# jduino.net
KiCad netlist of a schematic drawn in EAGLE
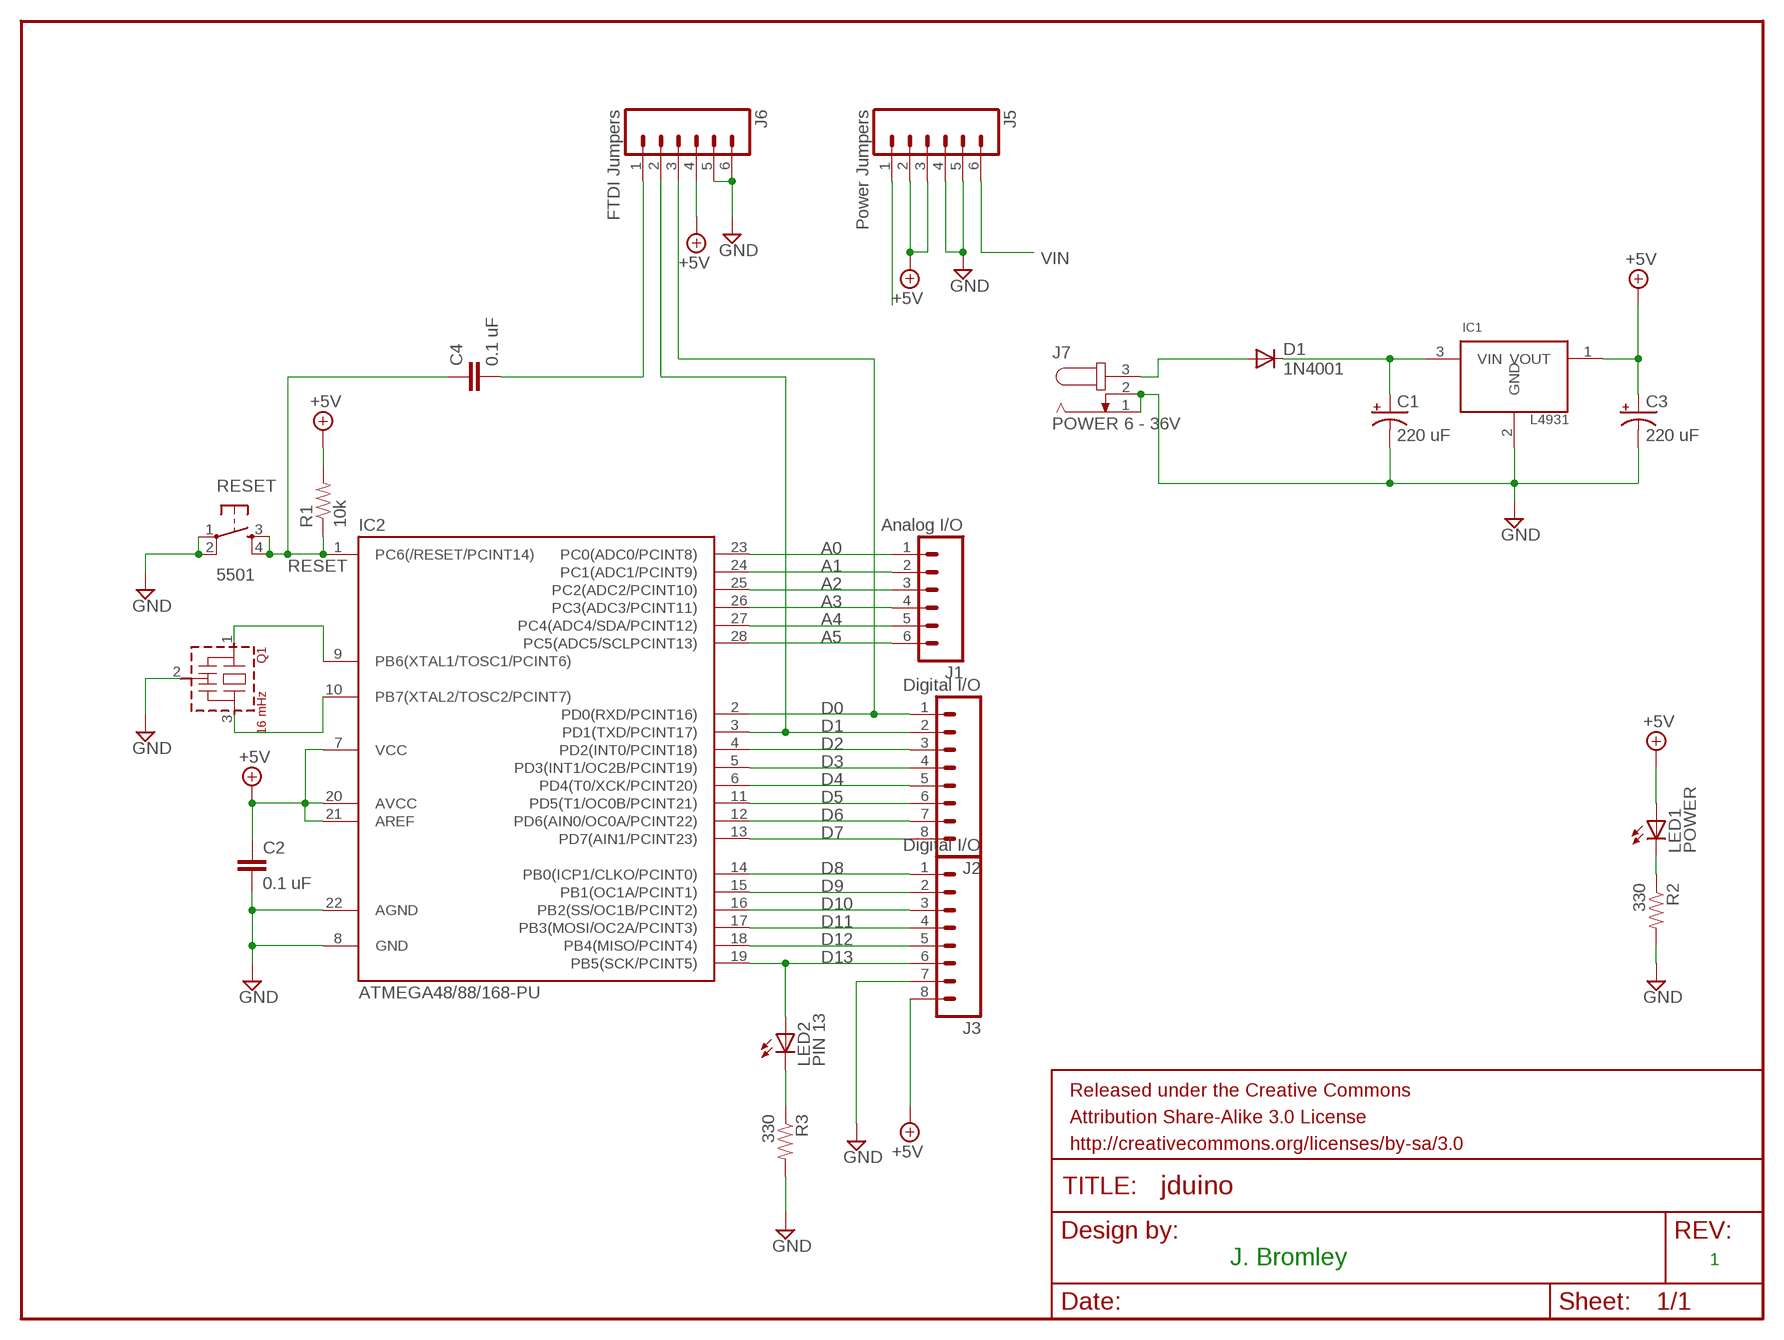
[diagram p0: schematic, sheet 1]

(export (version "E")
  (design (tool "Eeschema 10.0.6"))
  (components
    (comp (ref "C1")
      (value "220 uF")
      (footprint "eagle-import:CPOL-RADIAL-10UF-25V")
      (libsource (lib "eagle-import") (part "CAP_POLPTH2"))
    )
    (comp (ref "C2")
      (value "0.1 uF")
      (footprint "eagle-import:CAP-PTH-SMALL")
      (libsource (lib "eagle-import") (part "CAPPTH"))
    )
    (comp (ref "C3")
      (value "220 uF")
      (footprint "eagle-import:CPOL-RADIAL-10UF-25V")
      (libsource (lib "eagle-import") (part "CAP_POLPTH2"))
    )
    (comp (ref "C4")
      (value "0.1 uF")
      (footprint "eagle-import:CAP-PTH-SMALL")
      (libsource (lib "eagle-import") (part "CAPPTH"))
    )
    (comp (ref "D1")
      (value "1N4001")
      (footprint "eagle-import:DIODE-1N4001")
      (libsource (lib "eagle-import") (part "DIODEPTH"))
    )
    (comp (ref "IC1")
      (value "L4931")
      (footprint "eagle-import:TO-92")
      (libsource (lib "eagle-import") (part "L4931"))
    )
    (comp (ref "IC2")
      (value "ATMEGA48/88/168-PU")
      (footprint "eagle-import:DIL28-3")
      (libsource (lib "eagle-import") (part "ATMEGA48/88/168-PU"))
    )
    (comp (ref "J1")
      (value "Analog I/O")
      (footprint "eagle-import:1X06")
      (libsource (lib "eagle-import") (part "M06SIP"))
    )
    (comp (ref "J2")
      (value "Digital I/O")
      (footprint "eagle-import:1X08")
      (libsource (lib "eagle-import") (part "M08"))
    )
    (comp (ref "J3")
      (value "Digital I/O")
      (footprint "eagle-import:1X08")
      (libsource (lib "eagle-import") (part "M08"))
    )
    (comp (ref "J5")
      (value "Power Jumpers")
      (footprint "eagle-import:1X06")
      (libsource (lib "eagle-import") (part "M06SIP"))
    )
    (comp (ref "J6")
      (value "FTDI Jumpers")
      (footprint "eagle-import:1X06")
      (libsource (lib "eagle-import") (part "M06SIP"))
    )
    (comp (ref "J7")
      (value "POWER 6 - 36V")
      (footprint "eagle-import:SPC4078")
      (libsource (lib "eagle-import") (part "JACK-PLUG1"))
    )
    (comp (ref "LED1")
      (value "POWER")
      (footprint "eagle-import:LED3MM")
      (libsource (lib "eagle-import") (part "LED3MM"))
    )
    (comp (ref "LED2")
      (value "PIN 13")
      (footprint "eagle-import:LED3MM")
      (libsource (lib "eagle-import") (part "LED3MM"))
    )
    (comp (ref "Q1")
      (value "16 mHz")
      (footprint "eagle-import:CSTLS_X")
      (libsource (lib "eagle-import") (part "CSTLS_X"))
    )
    (comp (ref "R1")
      (value "10k")
      (footprint "eagle-import:AXIAL-0.3")
      (libsource (lib "eagle-import") (part "RESISTORAXIAL-0.3"))
    )
    (comp (ref "R2")
      (value "330")
      (footprint "eagle-import:AXIAL-0.3")
      (libsource (lib "eagle-import") (part "SparkFun-Resistors_RESISTORAXIAL-0.3"))
    )
    (comp (ref "R3")
      (value "330")
      (footprint "eagle-import:AXIAL-0.3")
      (libsource (lib "eagle-import") (part "SparkFun-Resistors_RESISTORAXIAL-0.3"))
    )
    (comp (ref "RESET")
      (value "5501")
      (footprint "eagle-import:TACTILE-PTH")
      (libsource (lib "eagle-import") (part "TAC_SWITCHPTH"))
    )
  )
  (nets
    (net (code "1") (name "+5V") (class "Default")
      (node (ref "C2") (pin "1") (pinfunction "1_1") (pintype "passive"))
      (node (ref "C3") (pin "1") (pinfunction "+_1") (pintype "passive"))
      (node (ref "IC1") (pin "1") (pinfunction "VOUT_1") (pintype "bidirectional"))
      (node (ref "IC2") (pin "20") (pinfunction "AVCC_20") (pintype "passive"))
      (node (ref "IC2") (pin "21") (pinfunction "AREF_21") (pintype "passive"))
      (node (ref "IC2") (pin "7") (pinfunction "VCC_7") (pintype "power_in"))
      (node (ref "J3") (pin "8") (pinfunction "8_8") (pintype "passive"))
      (node (ref "J5") (pin "2") (pinfunction "2_2") (pintype "passive"))
      (node (ref "J5") (pin "3") (pinfunction "3_3") (pintype "passive"))
      (node (ref "J6") (pin "4") (pinfunction "4_4") (pintype "passive"))
      (node (ref "LED1") (pin "A") (pinfunction "A_A") (pintype "passive"))
      (node (ref "R1") (pin "P$2") (pinfunction "2_P$2") (pintype "passive"))
    )
    (net (code "2") (name "/A0") (class "Default")
      (node (ref "IC2") (pin "23") (pinfunction "PC0(ADC0/PCINT8)_23") (pintype "bidirectional"))
      (node (ref "J1") (pin "1") (pinfunction "1_1") (pintype "passive"))
    )
    (net (code "3") (name "/A1") (class "Default")
      (node (ref "IC2") (pin "24") (pinfunction "PC1(ADC1/PCINT9)_24") (pintype "bidirectional"))
      (node (ref "J1") (pin "2") (pinfunction "2_2") (pintype "passive"))
    )
    (net (code "4") (name "/A2") (class "Default")
      (node (ref "IC2") (pin "25") (pinfunction "PC2(ADC2/PCINT10)_25") (pintype "bidirectional"))
      (node (ref "J1") (pin "3") (pinfunction "3_3") (pintype "passive"))
    )
    (net (code "5") (name "/A3") (class "Default")
      (node (ref "IC2") (pin "26") (pinfunction "PC3(ADC3/PCINT11)_26") (pintype "bidirectional"))
      (node (ref "J1") (pin "4") (pinfunction "4_4") (pintype "passive"))
    )
    (net (code "6") (name "/A4") (class "Default")
      (node (ref "IC2") (pin "27") (pinfunction "PC4(ADC4/SDA/PCINT12)_27") (pintype "bidirectional"))
      (node (ref "J1") (pin "5") (pinfunction "5_5") (pintype "passive"))
    )
    (net (code "7") (name "/A5") (class "Default")
      (node (ref "IC2") (pin "28") (pinfunction "PC5(ADC5/SCLPCINT13)_28") (pintype "bidirectional"))
      (node (ref "J1") (pin "6") (pinfunction "6_6") (pintype "passive"))
    )
    (net (code "8") (name "/D0") (class "Default")
      (node (ref "IC2") (pin "2") (pinfunction "PD0(RXD/PCINT16)_2") (pintype "bidirectional"))
      (node (ref "J2") (pin "1") (pinfunction "1_1") (pintype "passive"))
      (node (ref "J6") (pin "3") (pinfunction "3_3") (pintype "passive"))
    )
    (net (code "9") (name "/D1") (class "Default")
      (node (ref "IC2") (pin "3") (pinfunction "PD1(TXD/PCINT17)_3") (pintype "bidirectional"))
      (node (ref "J2") (pin "2") (pinfunction "2_2") (pintype "passive"))
      (node (ref "J6") (pin "2") (pinfunction "2_2") (pintype "passive"))
    )
    (net (code "10") (name "/D2") (class "Default")
      (node (ref "IC2") (pin "4") (pinfunction "PD2(INT0/PCINT18)_4") (pintype "bidirectional"))
      (node (ref "J2") (pin "3") (pinfunction "3_3") (pintype "passive"))
    )
    (net (code "11") (name "/D3") (class "Default")
      (node (ref "IC2") (pin "5") (pinfunction "PD3(INT1/OC2B/PCINT19)_5") (pintype "bidirectional"))
      (node (ref "J2") (pin "4") (pinfunction "4_4") (pintype "passive"))
    )
    (net (code "12") (name "/D4") (class "Default")
      (node (ref "IC2") (pin "6") (pinfunction "PD4(T0/XCK/PCINT20)_6") (pintype "bidirectional"))
      (node (ref "J2") (pin "5") (pinfunction "5_5") (pintype "passive"))
    )
    (net (code "13") (name "/D5") (class "Default")
      (node (ref "IC2") (pin "11") (pinfunction "PD5(T1/OC0B/PCINT21)_11") (pintype "bidirectional"))
      (node (ref "J2") (pin "6") (pinfunction "6_6") (pintype "passive"))
    )
    (net (code "14") (name "/D6") (class "Default")
      (node (ref "IC2") (pin "12") (pinfunction "PD6(AIN0/OC0A/PCINT22)_12") (pintype "bidirectional"))
      (node (ref "J2") (pin "7") (pinfunction "7_7") (pintype "passive"))
    )
    (net (code "15") (name "/D7") (class "Default")
      (node (ref "IC2") (pin "13") (pinfunction "PD7(AIN1/PCINT23)_13") (pintype "bidirectional"))
      (node (ref "J2") (pin "8") (pinfunction "8_8") (pintype "passive"))
    )
    (net (code "16") (name "/D8") (class "Default")
      (node (ref "IC2") (pin "14") (pinfunction "PB0(ICP1/CLKO/PCINT0)_14") (pintype "bidirectional"))
      (node (ref "J3") (pin "1") (pinfunction "1_1") (pintype "passive"))
    )
    (net (code "17") (name "/D9") (class "Default")
      (node (ref "IC2") (pin "15") (pinfunction "PB1(OC1A/PCINT1)_15") (pintype "bidirectional"))
      (node (ref "J3") (pin "2") (pinfunction "2_2") (pintype "passive"))
    )
    (net (code "18") (name "/D10") (class "Default")
      (node (ref "IC2") (pin "16") (pinfunction "PB2(SS/OC1B/PCINT2)_16") (pintype "bidirectional"))
      (node (ref "J3") (pin "3") (pinfunction "3_3") (pintype "passive"))
    )
    (net (code "19") (name "/D11") (class "Default")
      (node (ref "IC2") (pin "17") (pinfunction "PB3(MOSI/OC2A/PCINT3)_17") (pintype "bidirectional"))
      (node (ref "J3") (pin "4") (pinfunction "4_4") (pintype "passive"))
    )
    (net (code "20") (name "/D12") (class "Default")
      (node (ref "IC2") (pin "18") (pinfunction "PB4(MISO/PCINT4)_18") (pintype "bidirectional"))
      (node (ref "J3") (pin "5") (pinfunction "5_5") (pintype "passive"))
    )
    (net (code "21") (name "/D13") (class "Default")
      (node (ref "IC2") (pin "19") (pinfunction "PB5(SCK/PCINT5)_19") (pintype "bidirectional"))
      (node (ref "J3") (pin "6") (pinfunction "6_6") (pintype "passive"))
      (node (ref "LED2") (pin "A") (pinfunction "A_A") (pintype "passive"))
    )
    (net (code "22") (name "/RESET") (class "Default")
      (node (ref "C4") (pin "1") (pinfunction "1_1") (pintype "passive"))
      (node (ref "IC2") (pin "1") (pinfunction "PC6(/RESET/PCINT14)_1") (pintype "bidirectional"))
      (node (ref "J5") (pin "1") (pinfunction "1_1") (pintype "passive"))
      (node (ref "R1") (pin "P$1") (pinfunction "1_P$1") (pintype "passive"))
      (node (ref "RESET") (pin "3") (pinfunction "3_3") (pintype "passive"))
      (node (ref "RESET") (pin "4") (pinfunction "4_4") (pintype "passive"))
    )
    (net (code "23") (name "/VIN") (class "Default")
      (node (ref "J5") (pin "6") (pinfunction "6_6") (pintype "passive"))
    )
    (net (code "24") (name "GND") (class "Default")
      (node (ref "C1") (pin "2") (pinfunction "-_2") (pintype "passive"))
      (node (ref "C2") (pin "2") (pinfunction "2_2") (pintype "passive"))
      (node (ref "C3") (pin "2") (pinfunction "-_2") (pintype "passive"))
      (node (ref "IC1") (pin "2") (pinfunction "GND_2") (pintype "power_in"))
      (node (ref "IC2") (pin "22") (pinfunction "AGND_22") (pintype "power_in"))
      (node (ref "IC2") (pin "8") (pinfunction "GND_8") (pintype "power_in"))
      (node (ref "J3") (pin "7") (pinfunction "7_7") (pintype "passive"))
      (node (ref "J5") (pin "4") (pinfunction "4_4") (pintype "passive"))
      (node (ref "J5") (pin "5") (pinfunction "5_5") (pintype "passive"))
      (node (ref "J6") (pin "5") (pinfunction "5_5") (pintype "passive"))
      (node (ref "J6") (pin "6") (pinfunction "6_6") (pintype "passive"))
      (node (ref "J7") (pin "1") (pinfunction "1_1") (pintype "passive"))
      (node (ref "J7") (pin "2") (pinfunction "2_2") (pintype "passive"))
      (node (ref "Q1") (pin "2") (pinfunction "VSS_2") (pintype "power_in"))
      (node (ref "R2") (pin "P$2") (pinfunction "2_P$2") (pintype "passive"))
      (node (ref "R3") (pin "P$2") (pinfunction "2_P$2") (pintype "passive"))
      (node (ref "RESET") (pin "1") (pinfunction "1_1") (pintype "passive"))
      (node (ref "RESET") (pin "2") (pinfunction "2_2") (pintype "passive"))
    )
    (net (code "25") (name "Net-(C1-+)") (class "Default")
      (node (ref "C1") (pin "1") (pinfunction "+_1") (pintype "passive"))
      (node (ref "D1") (pin "C") (pinfunction "C_C") (pintype "passive"))
      (node (ref "IC1") (pin "3") (pinfunction "VIN_3") (pintype "input"))
    )
    (net (code "26") (name "Net-(C4-Pad2)") (class "Default")
      (node (ref "C4") (pin "2") (pinfunction "2_2") (pintype "passive"))
      (node (ref "J6") (pin "1") (pinfunction "1_1") (pintype "passive"))
    )
    (net (code "27") (name "Net-(D1-PadA)") (class "Default")
      (node (ref "D1") (pin "A") (pinfunction "A_A") (pintype "passive"))
      (node (ref "J7") (pin "3") (pinfunction "3_3") (pintype "passive"))
    )
    (net (code "28") (name "Net-(IC2-PB6(XTAL1{slash}TOSC1{slash}PCINT6))") (class "Default")
      (node (ref "IC2") (pin "9") (pinfunction "PB6(XTAL1/TOSC1/PCINT6)_9") (pintype "bidirectional"))
      (node (ref "Q1") (pin "1") (pinfunction "1_1") (pintype "output"))
    )
    (net (code "29") (name "Net-(IC2-PB7(XTAL2{slash}TOSC2{slash}PCINT7))") (class "Default")
      (node (ref "IC2") (pin "10") (pinfunction "PB7(XTAL2/TOSC2/PCINT7)_10") (pintype "bidirectional"))
      (node (ref "Q1") (pin "3") (pinfunction "3_3") (pintype "input"))
    )
    (net (code "30") (name "Net-(LED1-C)") (class "Default")
      (node (ref "LED1") (pin "K") (pinfunction "C_K") (pintype "passive"))
      (node (ref "R2") (pin "P$1") (pinfunction "1_P$1") (pintype "passive"))
    )
    (net (code "31") (name "Net-(LED2-C)") (class "Default")
      (node (ref "LED2") (pin "K") (pinfunction "C_K") (pintype "passive"))
      (node (ref "R3") (pin "P$1") (pinfunction "1_P$1") (pintype "passive"))
    )
  )
)
